# VentillatorCircuit.net
KiCad netlist of a schematic drawn in EAGLE
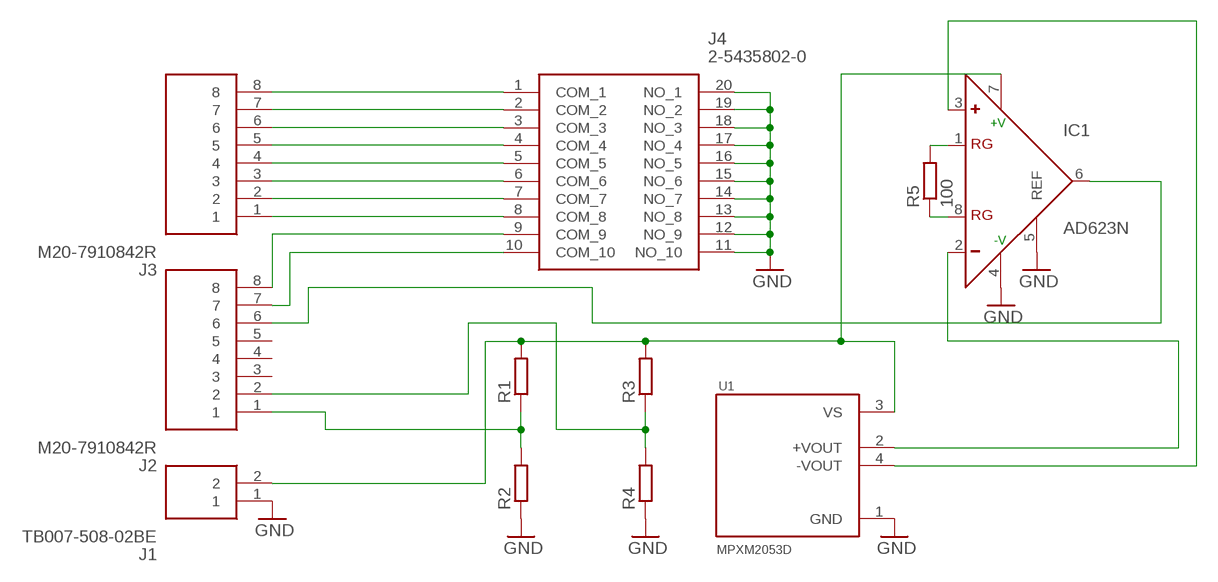
[diagram p0: schematic, sheet 1]

(export (version "E")
  (design (tool "Eeschema 10.0.6"))
  (components
    (comp (ref "IC1")
      (value "AD623N")
      (footprint "eagle-import:DIL08")
      (fields (field (name "MF") "ALTERA CORPORATION") (field (name "MPN") "AD623ANZ"))
      (libsource (lib "eagle-import") (part "AD623N"))
    )
    (comp (ref "J1")
      (value "TB007-508-02BE")
      (footprint "eagle-import:TB00750802BE")
      (fields (field (name "MOUSER_PART_NUMBER") "490-TB007-508-02BE"))
      (libsource (lib "eagle-import") (part "TB007-508-02BE"))
    )
    (comp (ref "J2")
      (value "M20-7910842R")
      (footprint "eagle-import:M207910842R")
      (fields (field (name "MOUSER_PART_NUMBER") "855-M20-7910842R"))
      (libsource (lib "eagle-import") (part "M20-7910842R"))
    )
    (comp (ref "J3")
      (value "M20-7910842R")
      (footprint "eagle-import:M207910842R")
      (fields (field (name "MOUSER_PART_NUMBER") "855-M20-7910842R"))
      (libsource (lib "eagle-import") (part "M20-7910842R"))
    )
    (comp (ref "J4")
      (value "2-5435802-0")
      (footprint "eagle-import:254358020")
      (fields (field (name "MOUSER_PART_NUMBER") "506-2-5435802-0"))
      (libsource (lib "eagle-import") (part "2-5435802-0"))
    )
    (comp (ref "R1")
      (value "R-EU_0207/12")
      (footprint "eagle-import:0207_12")
      (libsource (lib "eagle-import") (part "R-EU_0207/12"))
    )
    (comp (ref "R2")
      (value "R-EU_0207/12")
      (footprint "eagle-import:0207_12")
      (libsource (lib "eagle-import") (part "R-EU_0207/12"))
    )
    (comp (ref "R3")
      (value "R-EU_0207/12")
      (footprint "eagle-import:0207_12")
      (libsource (lib "eagle-import") (part "R-EU_0207/12"))
    )
    (comp (ref "R4")
      (value "R-EU_0207/12")
      (footprint "eagle-import:0207_12")
      (libsource (lib "eagle-import") (part "R-EU_0207/12"))
    )
    (comp (ref "R5")
      (value "100")
      (footprint "eagle-import:0207_12")
      (libsource (lib "eagle-import") (part "R-EU_0207/12"))
    )
    (comp (ref "U1")
      (value "MPXM2053D")
      (footprint "eagle-import:SOT127P1219X419-5N")
      (fields (field (name "MF") "Freescale Semiconductor"))
      (libsource (lib "eagle-import") (part "MPXM2053D"))
    )
  )
  (nets
    (net (code "1") (name "GND") (class "Default")
      (node (ref "IC1") (pin "4") (pinfunction "-V_4") (pintype "power_in"))
      (node (ref "IC1") (pin "5") (pinfunction "REF_5") (pintype "passive"))
      (node (ref "J1") (pin "1") (pinfunction "1_1") (pintype "bidirectional"))
      (node (ref "J4") (pin "11") (pinfunction "NO_10_11") (pintype "bidirectional"))
      (node (ref "J4") (pin "12") (pinfunction "NO_9_12") (pintype "bidirectional"))
      (node (ref "J4") (pin "13") (pinfunction "NO_8_13") (pintype "bidirectional"))
      (node (ref "J4") (pin "14") (pinfunction "NO_7_14") (pintype "bidirectional"))
      (node (ref "J4") (pin "15") (pinfunction "NO_6_15") (pintype "bidirectional"))
      (node (ref "J4") (pin "16") (pinfunction "NO_5_16") (pintype "bidirectional"))
      (node (ref "J4") (pin "17") (pinfunction "NO_4_17") (pintype "bidirectional"))
      (node (ref "J4") (pin "18") (pinfunction "NO_3_18") (pintype "bidirectional"))
      (node (ref "J4") (pin "19") (pinfunction "NO_2_19") (pintype "bidirectional"))
      (node (ref "J4") (pin "20") (pinfunction "NO_1_20") (pintype "bidirectional"))
      (node (ref "R2") (pin "1") (pinfunction "1_1") (pintype "passive"))
      (node (ref "R4") (pin "1") (pinfunction "1_1") (pintype "passive"))
      (node (ref "U1") (pin "1") (pinfunction "GND_1") (pintype "power_in"))
    )
    (net (code "2") (name "Net-(IC1-+)") (class "Default")
      (node (ref "IC1") (pin "3") (pinfunction "+_3") (pintype "input"))
      (node (ref "U1") (pin "4") (pinfunction "-VOUT_4") (pintype "output"))
    )
    (net (code "3") (name "Net-(IC1-+V)") (class "Default")
      (node (ref "IC1") (pin "7") (pinfunction "+V_7") (pintype "power_in"))
      (node (ref "J1") (pin "2") (pinfunction "2_2") (pintype "bidirectional"))
      (node (ref "R1") (pin "2") (pinfunction "2_2") (pintype "passive"))
      (node (ref "R3") (pin "2") (pinfunction "2_2") (pintype "passive"))
      (node (ref "U1") (pin "3") (pinfunction "VS_3") (pintype "power_in"))
    )
    (net (code "4") (name "Net-(IC1--)") (class "Default")
      (node (ref "IC1") (pin "2") (pinfunction "-_2") (pintype "input"))
      (node (ref "U1") (pin "2") (pinfunction "+VOUT_2") (pintype "output"))
    )
    (net (code "5") (name "Net-(IC1-OUT)") (class "Default")
      (node (ref "IC1") (pin "6") (pinfunction "OUT_6") (pintype "output"))
      (node (ref "J2") (pin "6") (pinfunction "6_6") (pintype "bidirectional"))
    )
    (net (code "6") (name "Net-(IC1-RG-Pad1)") (class "Default")
      (node (ref "IC1") (pin "1") (pinfunction "RG_1") (pintype "passive"))
      (node (ref "R5") (pin "2") (pinfunction "2_2") (pintype "passive"))
    )
    (net (code "7") (name "Net-(IC1-RG-Pad8)") (class "Default")
      (node (ref "IC1") (pin "8") (pinfunction "RG_8") (pintype "passive"))
      (node (ref "R5") (pin "1") (pinfunction "1_1") (pintype "passive"))
    )
    (net (code "8") (name "Net-(J2-Pad1)") (class "Default")
      (node (ref "J2") (pin "1") (pinfunction "1_1") (pintype "bidirectional"))
      (node (ref "R1") (pin "1") (pinfunction "1_1") (pintype "passive"))
      (node (ref "R2") (pin "2") (pinfunction "2_2") (pintype "passive"))
    )
    (net (code "9") (name "Net-(J2-Pad2)") (class "Default")
      (node (ref "J2") (pin "2") (pinfunction "2_2") (pintype "bidirectional"))
      (node (ref "R3") (pin "1") (pinfunction "1_1") (pintype "passive"))
      (node (ref "R4") (pin "2") (pinfunction "2_2") (pintype "passive"))
    )
    (net (code "10") (name "Net-(J4-COM_1)") (class "Default")
      (node (ref "J3") (pin "8") (pinfunction "8_8") (pintype "bidirectional"))
      (node (ref "J4") (pin "1") (pinfunction "COM_1_1") (pintype "bidirectional"))
    )
    (net (code "11") (name "Net-(J4-COM_2)") (class "Default")
      (node (ref "J3") (pin "7") (pinfunction "7_7") (pintype "bidirectional"))
      (node (ref "J4") (pin "2") (pinfunction "COM_2_2") (pintype "bidirectional"))
    )
    (net (code "12") (name "Net-(J4-COM_3)") (class "Default")
      (node (ref "J3") (pin "6") (pinfunction "6_6") (pintype "bidirectional"))
      (node (ref "J4") (pin "3") (pinfunction "COM_3_3") (pintype "bidirectional"))
    )
    (net (code "13") (name "Net-(J4-COM_4)") (class "Default")
      (node (ref "J3") (pin "5") (pinfunction "5_5") (pintype "bidirectional"))
      (node (ref "J4") (pin "4") (pinfunction "COM_4_4") (pintype "bidirectional"))
    )
    (net (code "14") (name "Net-(J4-COM_5)") (class "Default")
      (node (ref "J3") (pin "4") (pinfunction "4_4") (pintype "bidirectional"))
      (node (ref "J4") (pin "5") (pinfunction "COM_5_5") (pintype "bidirectional"))
    )
    (net (code "15") (name "Net-(J4-COM_6)") (class "Default")
      (node (ref "J3") (pin "3") (pinfunction "3_3") (pintype "bidirectional"))
      (node (ref "J4") (pin "6") (pinfunction "COM_6_6") (pintype "bidirectional"))
    )
    (net (code "16") (name "Net-(J4-COM_7)") (class "Default")
      (node (ref "J3") (pin "2") (pinfunction "2_2") (pintype "bidirectional"))
      (node (ref "J4") (pin "7") (pinfunction "COM_7_7") (pintype "bidirectional"))
    )
    (net (code "17") (name "Net-(J4-COM_8)") (class "Default")
      (node (ref "J3") (pin "1") (pinfunction "1_1") (pintype "bidirectional"))
      (node (ref "J4") (pin "8") (pinfunction "COM_8_8") (pintype "bidirectional"))
    )
    (net (code "18") (name "Net-(J4-COM_9)") (class "Default")
      (node (ref "J2") (pin "8") (pinfunction "8_8") (pintype "bidirectional"))
      (node (ref "J4") (pin "9") (pinfunction "COM_9_9") (pintype "bidirectional"))
    )
    (net (code "19") (name "Net-(J4-COM_10)") (class "Default")
      (node (ref "J2") (pin "7") (pinfunction "7_7") (pintype "bidirectional"))
      (node (ref "J4") (pin "10") (pinfunction "COM_10_10") (pintype "bidirectional"))
    )
    (net (code "20") (name "unconnected-(J2-Pad3)") (class "Default")
      (node (ref "J2") (pin "3") (pinfunction "3_3") (pintype "bidirectional"))
    )
    (net (code "21") (name "unconnected-(J2-Pad4)") (class "Default")
      (node (ref "J2") (pin "4") (pinfunction "4_4") (pintype "bidirectional"))
    )
    (net (code "22") (name "unconnected-(J2-Pad5)") (class "Default")
      (node (ref "J2") (pin "5") (pinfunction "5_5") (pintype "bidirectional"))
    )
  )
)
